# absolute_position.net
KiCad netlist of a schematic drawn in EAGLE
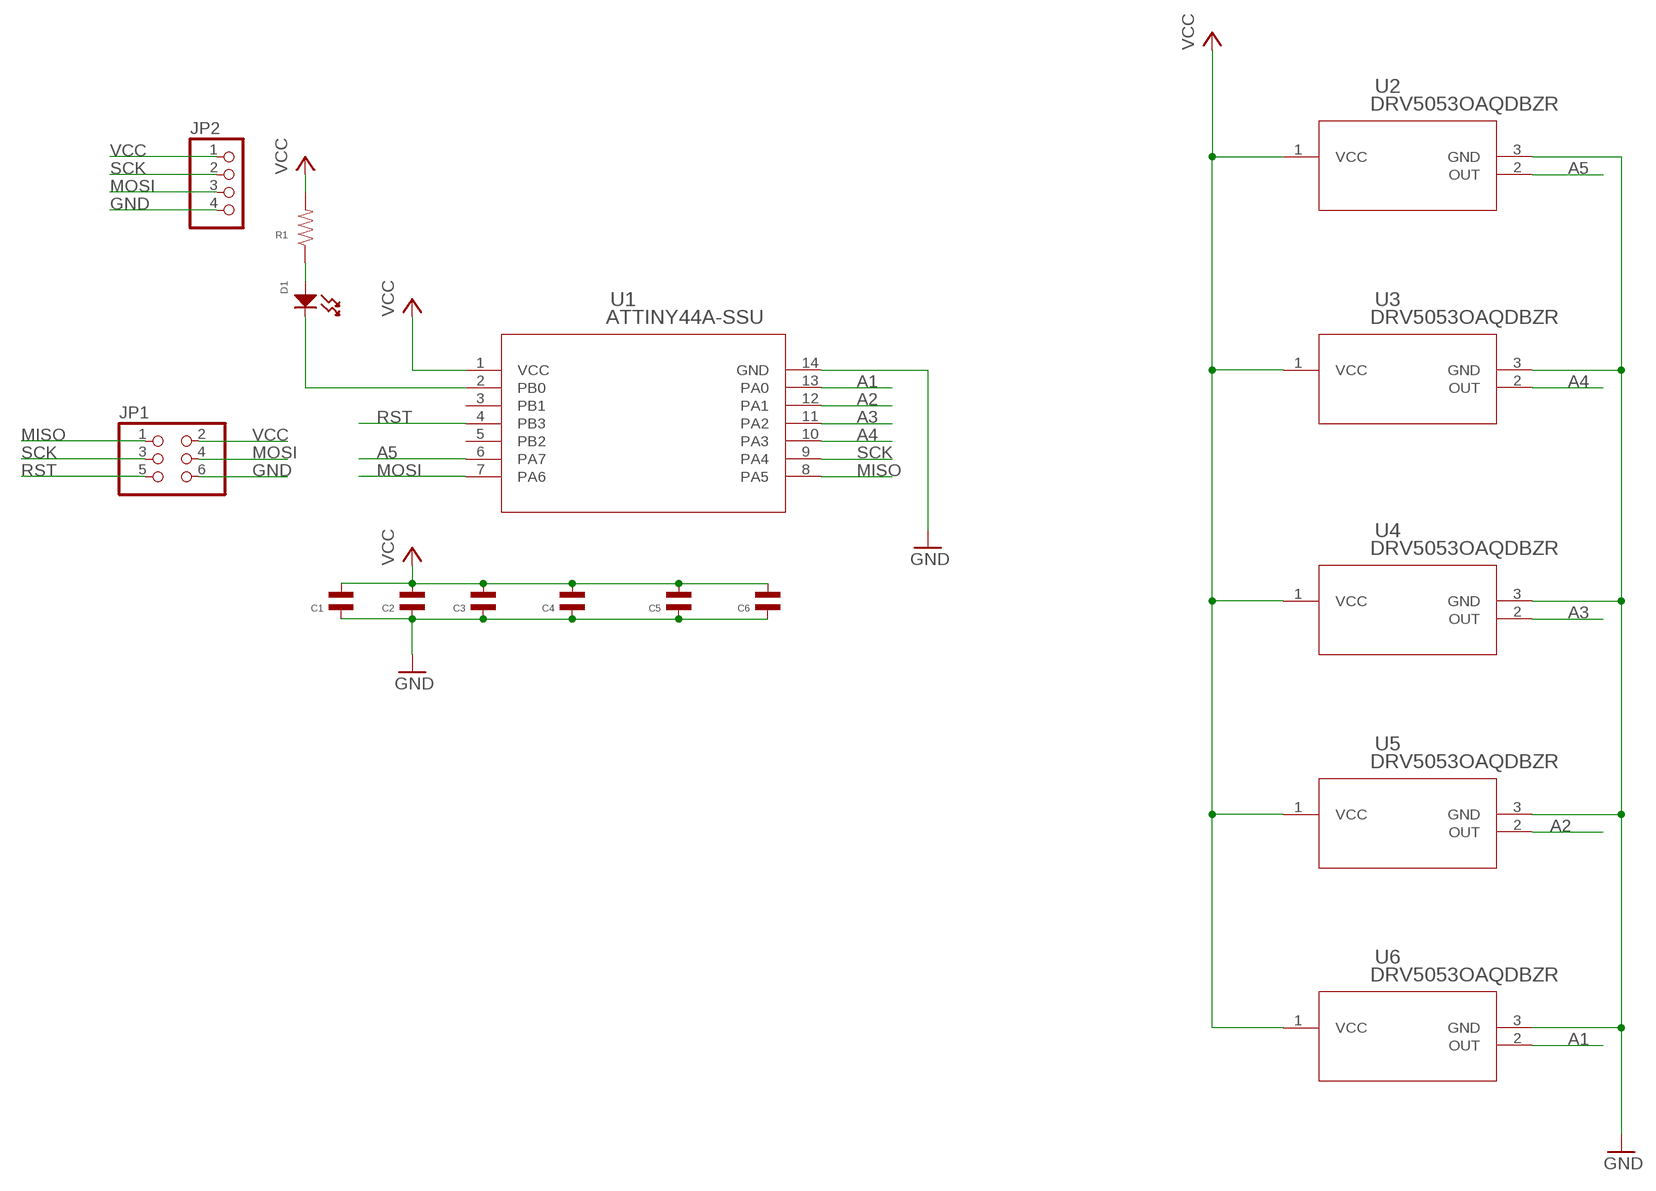
[diagram p0: schematic, sheet 1]

(export (version "E")
  (design (tool "Eeschema 10.0.6"))
  (components
    (comp (ref "C1")
      (value "CAPACITOR_NP_0603")
      (footprint "eagle-import:C0603")
      (libsource (lib "eagle-import") (part "CAPACITOR_NP_0603"))
    )
    (comp (ref "C2")
      (value "CAPACITOR_NP_0603")
      (footprint "eagle-import:C0603")
      (libsource (lib "eagle-import") (part "CAPACITOR_NP_0603"))
    )
    (comp (ref "C3")
      (value "CAPACITOR_NP_0603")
      (footprint "eagle-import:C0603")
      (libsource (lib "eagle-import") (part "CAPACITOR_NP_0603"))
    )
    (comp (ref "C4")
      (value "CAPACITOR_NP_0603")
      (footprint "eagle-import:C0603")
      (libsource (lib "eagle-import") (part "CAPACITOR_NP_0603"))
    )
    (comp (ref "C5")
      (value "CAPACITOR_NP_0603")
      (footprint "eagle-import:C0603")
      (libsource (lib "eagle-import") (part "CAPACITOR_NP_0603"))
    )
    (comp (ref "C6")
      (value "CAPACITOR_NP_0603")
      (footprint "eagle-import:C0603")
      (libsource (lib "eagle-import") (part "CAPACITOR_NP_0603"))
    )
    (comp (ref "D1")
      (value "LED_SINGLE-0603")
      (footprint "eagle-import:LED0603")
      (fields (field (name "HOUSEPART") "NO"))
      (libsource (lib "eagle-import") (part "LED_SINGLE-0603"))
    )
    (comp (ref "JP1")
      (value "PINHD-2X3")
      (footprint "eagle-import:2X03")
      (libsource (lib "eagle-import") (part "PINHD-2X3"))
    )
    (comp (ref "JP2")
      (value "PINHD-1X4")
      (footprint "eagle-import:1X04")
      (libsource (lib "eagle-import") (part "PINHD-1X4"))
    )
    (comp (ref "R1")
      (value "RESISTOR_0603")
      (footprint "eagle-import:R0603")
      (libsource (lib "eagle-import") (part "RESISTOR_0603"))
    )
    (comp (ref "U1")
      (value "ATTINY44A-SSU")
      (footprint "eagle-import:14S1")
      (fields (field (name "MANUFACTURER_PART_NUMBER") "ATTINY44ASSU"))
      (libsource (lib "eagle-import") (part "ATTINY44A-SSU"))
    )
    (comp (ref "U2")
      (value "DRV5053OAQDBZR")
      (footprint "eagle-import:DBZ3")
      (libsource (lib "eagle-import") (part "DRV5053OAQDBZR"))
    )
    (comp (ref "U3")
      (value "DRV5053OAQDBZR")
      (footprint "eagle-import:DBZ3")
      (libsource (lib "eagle-import") (part "DRV5053OAQDBZR"))
    )
    (comp (ref "U4")
      (value "DRV5053OAQDBZR")
      (footprint "eagle-import:DBZ3")
      (libsource (lib "eagle-import") (part "DRV5053OAQDBZR"))
    )
    (comp (ref "U5")
      (value "DRV5053OAQDBZR")
      (footprint "eagle-import:DBZ3")
      (libsource (lib "eagle-import") (part "DRV5053OAQDBZR"))
    )
    (comp (ref "U6")
      (value "DRV5053OAQDBZR")
      (footprint "eagle-import:DBZ3")
      (libsource (lib "eagle-import") (part "DRV5053OAQDBZR"))
    )
  )
  (nets
    (net (code "1") (name "/A1") (class "Default")
      (node (ref "U1") (pin "13") (pinfunction "PA0_13") (pintype "passive"))
      (node (ref "U6") (pin "2") (pinfunction "OUT_2") (pintype "output"))
    )
    (net (code "2") (name "/A2") (class "Default")
      (node (ref "U1") (pin "12") (pinfunction "PA1_12") (pintype "passive"))
      (node (ref "U5") (pin "2") (pinfunction "OUT_2") (pintype "output"))
    )
    (net (code "3") (name "/A3") (class "Default")
      (node (ref "U1") (pin "11") (pinfunction "PA2_11") (pintype "passive"))
      (node (ref "U4") (pin "2") (pinfunction "OUT_2") (pintype "output"))
    )
    (net (code "4") (name "/A4") (class "Default")
      (node (ref "U1") (pin "10") (pinfunction "PA3_10") (pintype "passive"))
      (node (ref "U3") (pin "2") (pinfunction "OUT_2") (pintype "output"))
    )
    (net (code "5") (name "/A5") (class "Default")
      (node (ref "U1") (pin "6") (pinfunction "PA7_6") (pintype "passive"))
      (node (ref "U2") (pin "2") (pinfunction "OUT_2") (pintype "output"))
    )
    (net (code "6") (name "/MISO") (class "Default")
      (node (ref "JP1") (pin "1") (pinfunction "1_1") (pintype "passive"))
      (node (ref "U1") (pin "8") (pinfunction "PA5_8") (pintype "passive"))
    )
    (net (code "7") (name "/MOSI") (class "Default")
      (node (ref "JP1") (pin "4") (pinfunction "4_4") (pintype "passive"))
      (node (ref "JP2") (pin "3") (pinfunction "3_3") (pintype "passive"))
      (node (ref "U1") (pin "7") (pinfunction "PA6_7") (pintype "passive"))
    )
    (net (code "8") (name "/RST") (class "Default")
      (node (ref "JP1") (pin "5") (pinfunction "5_5") (pintype "passive"))
      (node (ref "U1") (pin "4") (pinfunction "PB3_4") (pintype "passive"))
    )
    (net (code "9") (name "/SCK") (class "Default")
      (node (ref "JP1") (pin "3") (pinfunction "3_3") (pintype "passive"))
      (node (ref "JP2") (pin "2") (pinfunction "2_2") (pintype "passive"))
      (node (ref "U1") (pin "9") (pinfunction "PA4_9") (pintype "passive"))
    )
    (net (code "10") (name "GND") (class "Default")
      (node (ref "C1") (pin "P$1") (pinfunction "P$1_P$1") (pintype "passive"))
      (node (ref "C2") (pin "P$1") (pinfunction "P$1_P$1") (pintype "passive"))
      (node (ref "C3") (pin "P$1") (pinfunction "P$1_P$1") (pintype "passive"))
      (node (ref "C4") (pin "P$1") (pinfunction "P$1_P$1") (pintype "passive"))
      (node (ref "C5") (pin "P$1") (pinfunction "P$1_P$1") (pintype "passive"))
      (node (ref "C6") (pin "P$1") (pinfunction "P$1_P$1") (pintype "passive"))
      (node (ref "JP1") (pin "6") (pinfunction "6_6") (pintype "passive"))
      (node (ref "JP2") (pin "4") (pinfunction "4_4") (pintype "passive"))
      (node (ref "U1") (pin "14") (pinfunction "GND_14") (pintype "passive"))
      (node (ref "U2") (pin "3") (pinfunction "GND_3") (pintype "power_in"))
      (node (ref "U3") (pin "3") (pinfunction "GND_3") (pintype "power_in"))
      (node (ref "U4") (pin "3") (pinfunction "GND_3") (pintype "power_in"))
      (node (ref "U5") (pin "3") (pinfunction "GND_3") (pintype "power_in"))
      (node (ref "U6") (pin "3") (pinfunction "GND_3") (pintype "power_in"))
    )
    (net (code "11") (name "Net-(D1-PadANODE)") (class "Default")
      (node (ref "D1") (pin "ANODE") (pinfunction "ANODE_ANODE") (pintype "power_in"))
      (node (ref "R1") (pin "P$1") (pinfunction "P$1_P$1") (pintype "passive"))
    )
    (net (code "12") (name "Net-(U1-PB0)") (class "Default")
      (node (ref "D1") (pin "CATHODE") (pinfunction "CATHODE_CATHODE") (pintype "power_in"))
      (node (ref "U1") (pin "2") (pinfunction "PB0_2") (pintype "passive"))
    )
    (net (code "13") (name "VCC") (class "Default")
      (node (ref "C1") (pin "P$2") (pinfunction "P$2_P$2") (pintype "passive"))
      (node (ref "C2") (pin "P$2") (pinfunction "P$2_P$2") (pintype "passive"))
      (node (ref "C3") (pin "P$2") (pinfunction "P$2_P$2") (pintype "passive"))
      (node (ref "C4") (pin "P$2") (pinfunction "P$2_P$2") (pintype "passive"))
      (node (ref "C5") (pin "P$2") (pinfunction "P$2_P$2") (pintype "passive"))
      (node (ref "C6") (pin "P$2") (pinfunction "P$2_P$2") (pintype "passive"))
      (node (ref "JP1") (pin "2") (pinfunction "2_2") (pintype "passive"))
      (node (ref "JP2") (pin "1") (pinfunction "1_1") (pintype "passive"))
      (node (ref "R1") (pin "P$2") (pinfunction "P$2_P$2") (pintype "passive"))
      (node (ref "U1") (pin "1") (pinfunction "VCC_1") (pintype "passive"))
      (node (ref "U2") (pin "1") (pinfunction "VCC_1") (pintype "power_in"))
      (node (ref "U3") (pin "1") (pinfunction "VCC_1") (pintype "power_in"))
      (node (ref "U4") (pin "1") (pinfunction "VCC_1") (pintype "power_in"))
      (node (ref "U5") (pin "1") (pinfunction "VCC_1") (pintype "power_in"))
      (node (ref "U6") (pin "1") (pinfunction "VCC_1") (pintype "power_in"))
    )
    (net (code "14") (name "unconnected-(U1-PB1-Pad3)") (class "Default")
      (node (ref "U1") (pin "3") (pinfunction "PB1_3") (pintype "passive"))
    )
    (net (code "15") (name "unconnected-(U1-PB2-Pad5)") (class "Default")
      (node (ref "U1") (pin "5") (pinfunction "PB2_5") (pintype "passive"))
    )
  )
)
